# ultra-violet-tooth-sensor-mk-2_4.net
KiCad netlist of a schematic drawn in EAGLE
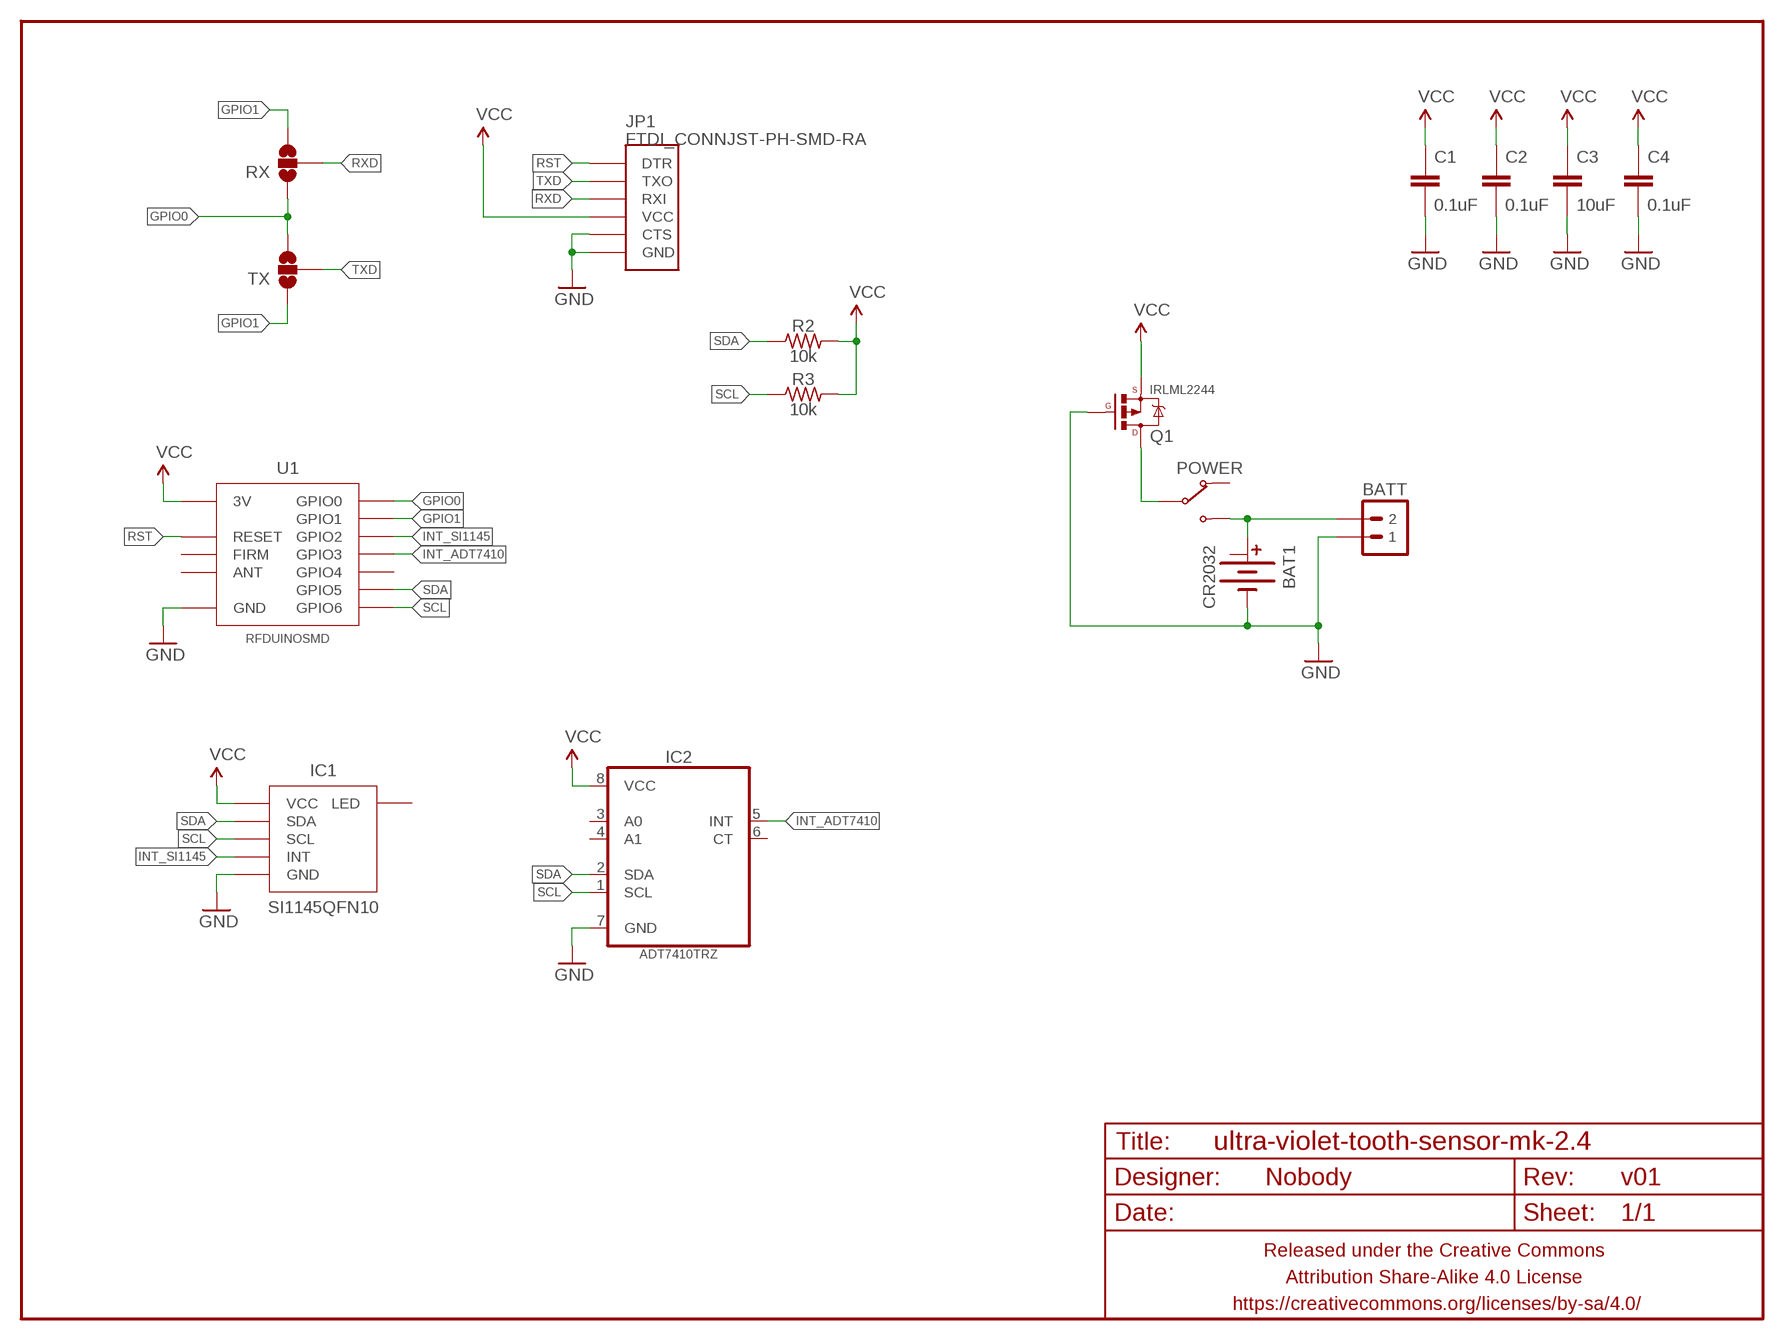
[diagram p0: schematic, sheet 1]

(export (version "E")
  (design (tool "Eeschema 10.0.6"))
  (components
    (comp (ref "BAT1")
      (value "CR2032")
      (footprint "eagle-import:BATTCON_20MM_MINE_STAHPIT")
      (libsource (lib "eagle-import") (part "BATTERY-COINCR2032_SMD_TIGHT"))
    )
    (comp (ref "BATT")
      (value "M02PTH-CENTERED-R+")
      (footprint "eagle-import:1X02-CENTER-R+")
      (libsource (lib "eagle-import") (part "M02PTH-CENTERED-R+"))
    )
    (comp (ref "C1")
      (value "0.1uF")
      (footprint "eagle-import:C0805")
      (libsource (lib "eagle-import") (part "CAPACITOR-CERAMICC0805"))
    )
    (comp (ref "C2")
      (value "0.1uF")
      (footprint "eagle-import:C0603")
      (libsource (lib "eagle-import") (part "CAPACITOR-CERAMICC0603"))
    )
    (comp (ref "C3")
      (value "10uF")
      (footprint "eagle-import:C1206")
      (libsource (lib "eagle-import") (part "CAPACITOR-CERAMICC1206"))
    )
    (comp (ref "C4")
      (value "0.1uF")
      (footprint "eagle-import:C0603")
      (libsource (lib "eagle-import") (part "CAPACITOR-CERAMICC0603"))
    )
    (comp (ref "FRAME1")
      (value "FRAME-LETTERNO_PACKAGE")
      (footprint "eagle-import:DUMMY")
      (fields (field (name "DESIGNER") "Nobody"))
      (libsource (lib "eagle-import") (part "FRAME-LETTERNO_PACKAGE"))
    )
    (comp (ref "IC1")
      (value "SI1145QFN10")
      (footprint "eagle-import:SI1145")
      (libsource (lib "eagle-import") (part "SI1145QFN10"))
    )
    (comp (ref "IC2")
      (value "ADT7410TRZ")
      (footprint "eagle-import:SOIC127P600X175-8N")
      (libsource (lib "eagle-import") (part "ADT7410TRZSOIC8N"))
    )
    (comp (ref "JP1")
      (value "FTDI_CONNJST-PH-SMD-RA")
      (footprint "eagle-import:AVRISP-JST-6-PH-RA-SMD")
      (libsource (lib "eagle-import") (part "FTDI_CONNJST-PH-SMD-RA"))
    )
    (comp (ref "POWER")
      (value "SWITCH-SPDTPTH-RA-2.54MM")
      (footprint "eagle-import:SPDT-RA-2.54MM")
      (libsource (lib "eagle-import") (part "SWITCH-SPDTPTH-RA-2.54MM"))
    )
    (comp (ref "Q1")
      (value "IRLML2244")
      (footprint "eagle-import:SOT23-3")
      (libsource (lib "eagle-import") (part "MOSFET-PCHANNELIRLML2244"))
    )
    (comp (ref "R2")
      (value "10k")
      (footprint "eagle-import:R0603")
      (libsource (lib "eagle-import") (part "RESISTORR0603"))
    )
    (comp (ref "R3")
      (value "10k")
      (footprint "eagle-import:R0603")
      (libsource (lib "eagle-import") (part "RESISTORR0603"))
    )
    (comp (ref "RX")
      (value "JUMPER-PAD-3-NOFULL_BOX_SILK")
      (footprint "eagle-import:PAD-JUMPER-3-NO_YES_SILK_FULL_BOX")
      (libsource (lib "eagle-import") (part "JUMPER-PAD-3-NOFULL_BOX_SILK"))
    )
    (comp (ref "TX")
      (value "JUMPER-PAD-3-NOFULL_BOX_SILK")
      (footprint "eagle-import:PAD-JUMPER-3-NO_YES_SILK_FULL_BOX")
      (libsource (lib "eagle-import") (part "JUMPER-PAD-3-NOFULL_BOX_SILK"))
    )
    (comp (ref "U1")
      (value "RFDUINOSMD")
      (footprint "eagle-import:RFDUINO-SMD")
      (libsource (lib "eagle-import") (part "RFDUINOSMD"))
    )
  )
  (nets
    (net (code "1") (name "GND") (class "Default")
      (node (ref "BAT1") (pin "BOTTOM") (pinfunction "-_BOTTOM") (pintype "bidirectional"))
      (node (ref "BATT") (pin "1") (pinfunction "1_1") (pintype "passive"))
      (node (ref "C1") (pin "2") (pinfunction "2_2") (pintype "passive"))
      (node (ref "C2") (pin "2") (pinfunction "2_2") (pintype "passive"))
      (node (ref "C3") (pin "2") (pinfunction "2_2") (pintype "passive"))
      (node (ref "C4") (pin "2") (pinfunction "2_2") (pintype "passive"))
      (node (ref "IC1") (pin "GND") (pinfunction "GND_GND") (pintype "bidirectional"))
      (node (ref "IC2") (pin "7") (pinfunction "GND_7") (pintype "passive"))
      (node (ref "JP1") (pin "CTS") (pinfunction "CTS_CTS") (pintype "bidirectional"))
      (node (ref "JP1") (pin "GND") (pinfunction "GND_GND") (pintype "bidirectional"))
      (node (ref "Q1") (pin "1") (pinfunction "G_1") (pintype "passive"))
      (node (ref "U1") (pin "GND@1") (pinfunction "GND_GND@1") (pintype "bidirectional"))
      (node (ref "U1") (pin "GND@2") (pinfunction "GND_GND@2") (pintype "bidirectional"))
      (node (ref "U1") (pin "GND@3") (pinfunction "GND_GND@3") (pintype "bidirectional"))
      (node (ref "U1") (pin "GND@4") (pinfunction "GND_GND@4") (pintype "bidirectional"))
      (node (ref "U1") (pin "GND@5") (pinfunction "GND_GND@5") (pintype "bidirectional"))
      (node (ref "U1") (pin "GND@6") (pinfunction "GND_GND@6") (pintype "bidirectional"))
      (node (ref "U1") (pin "GND@7") (pinfunction "GND_GND@7") (pintype "bidirectional"))
      (node (ref "U1") (pin "GND@8") (pinfunction "GND_GND@8") (pintype "bidirectional"))
    )
    (net (code "2") (name "GPIO0") (class "Default")
      (node (ref "RX") (pin "1") (pinfunction "1_1") (pintype "passive"))
      (node (ref "TX") (pin "3") (pinfunction "3_3") (pintype "passive"))
      (node (ref "U1") (pin "GPIO0") (pinfunction "GPIO0_GPIO0") (pintype "bidirectional"))
    )
    (net (code "3") (name "GPIO1") (class "Default")
      (node (ref "RX") (pin "3") (pinfunction "3_3") (pintype "passive"))
      (node (ref "TX") (pin "1") (pinfunction "1_1") (pintype "passive"))
      (node (ref "U1") (pin "GPIO1") (pinfunction "GPIO1_GPIO1") (pintype "bidirectional"))
    )
    (net (code "4") (name "INT_ADT7410") (class "Default")
      (node (ref "IC2") (pin "5") (pinfunction "INT_5") (pintype "output"))
      (node (ref "U1") (pin "GPIO3") (pinfunction "GPIO3_GPIO3") (pintype "bidirectional"))
    )
    (net (code "5") (name "INT_SI1145") (class "Default")
      (node (ref "IC1") (pin "INT") (pinfunction "INT_INT") (pintype "bidirectional"))
      (node (ref "U1") (pin "GPIO2") (pinfunction "GPIO2_GPIO2") (pintype "bidirectional"))
    )
    (net (code "6") (name "Net-(BAT1-+)") (class "Default")
      (node (ref "BAT1") (pin "TOP@1") (pinfunction "+_TOP@1") (pintype "bidirectional"))
      (node (ref "BATT") (pin "2") (pinfunction "2_2") (pintype "passive"))
      (node (ref "POWER") (pin "3") (pinfunction "NO_3") (pintype "passive"))
    )
    (net (code "7") (name "Net-(POWER-COM)") (class "Default")
      (node (ref "POWER") (pin "2") (pinfunction "COM_2") (pintype "passive"))
      (node (ref "Q1") (pin "3") (pinfunction "D_3") (pintype "passive"))
    )
    (net (code "8") (name "RST") (class "Default")
      (node (ref "JP1") (pin "DTR") (pinfunction "DTR_DTR") (pintype "bidirectional"))
      (node (ref "U1") (pin "RESET") (pinfunction "RESET_RESET") (pintype "bidirectional"))
    )
    (net (code "9") (name "RXD") (class "Default")
      (node (ref "JP1") (pin "RXI") (pinfunction "RXI_RXI") (pintype "bidirectional"))
      (node (ref "RX") (pin "2") (pinfunction "2_2") (pintype "passive"))
    )
    (net (code "10") (name "SCL") (class "Default")
      (node (ref "IC1") (pin "SCL") (pinfunction "SCL_SCL") (pintype "bidirectional"))
      (node (ref "IC2") (pin "1") (pinfunction "SCL_1") (pintype "input"))
      (node (ref "R3") (pin "1") (pinfunction "1_1") (pintype "passive"))
      (node (ref "U1") (pin "GPIO6") (pinfunction "GPIO6_GPIO6") (pintype "bidirectional"))
    )
    (net (code "11") (name "SDA") (class "Default")
      (node (ref "IC1") (pin "SDA") (pinfunction "SDA_SDA") (pintype "bidirectional"))
      (node (ref "IC2") (pin "2") (pinfunction "SDA_2") (pintype "bidirectional"))
      (node (ref "R2") (pin "1") (pinfunction "1_1") (pintype "passive"))
      (node (ref "U1") (pin "GPIO5") (pinfunction "GPIO5_GPIO5") (pintype "bidirectional"))
    )
    (net (code "12") (name "TXD") (class "Default")
      (node (ref "JP1") (pin "TXO") (pinfunction "TXO_TXO") (pintype "bidirectional"))
      (node (ref "TX") (pin "2") (pinfunction "2_2") (pintype "passive"))
    )
    (net (code "13") (name "VCC") (class "Default")
      (node (ref "C1") (pin "1") (pinfunction "1_1") (pintype "passive"))
      (node (ref "C2") (pin "1") (pinfunction "1_1") (pintype "passive"))
      (node (ref "C3") (pin "1") (pinfunction "1_1") (pintype "passive"))
      (node (ref "C4") (pin "1") (pinfunction "1_1") (pintype "passive"))
      (node (ref "IC1") (pin "VCC@1") (pinfunction "VCC_VCC@1") (pintype "bidirectional"))
      (node (ref "IC1") (pin "VCC@2") (pinfunction "VCC_VCC@2") (pintype "bidirectional"))
      (node (ref "IC1") (pin "VCC@3") (pinfunction "VCC_VCC@3") (pintype "bidirectional"))
      (node (ref "IC2") (pin "8") (pinfunction "VCC_8") (pintype "power_in"))
      (node (ref "JP1") (pin "VCC") (pinfunction "VCC_VCC") (pintype "bidirectional"))
      (node (ref "Q1") (pin "2") (pinfunction "S_2") (pintype "passive"))
      (node (ref "R2") (pin "2") (pinfunction "2_2") (pintype "passive"))
      (node (ref "R3") (pin "2") (pinfunction "2_2") (pintype "passive"))
      (node (ref "U1") (pin "3V") (pinfunction "3V_3V") (pintype "bidirectional"))
    )
    (net (code "14") (name "unconnected-(BAT1-+1-PadTOP@2)") (class "Default")
      (node (ref "BAT1") (pin "TOP@2") (pinfunction "+1_TOP@2") (pintype "bidirectional"))
    )
    (net (code "15") (name "unconnected-(IC1-PadLED)") (class "Default")
      (node (ref "IC1") (pin "LED") (pinfunction "LED_LED") (pintype "bidirectional"))
    )
    (net (code "16") (name "unconnected-(IC2-A0-Pad3)") (class "Default")
      (node (ref "IC2") (pin "3") (pinfunction "A0_3") (pintype "input"))
    )
    (net (code "17") (name "unconnected-(IC2-A1-Pad4)") (class "Default")
      (node (ref "IC2") (pin "4") (pinfunction "A1_4") (pintype "input"))
    )
    (net (code "18") (name "unconnected-(IC2-CT-Pad6)") (class "Default")
      (node (ref "IC2") (pin "6") (pinfunction "CT_6") (pintype "output"))
    )
    (net (code "19") (name "unconnected-(POWER-NC-Pad1)") (class "Default")
      (node (ref "POWER") (pin "1") (pinfunction "NC_1") (pintype "passive"))
    )
    (net (code "20") (name "unconnected-(U1-FIRM-PadFACTORY)") (class "Default")
      (node (ref "U1") (pin "FACTORY") (pinfunction "FIRM_FACTORY") (pintype "bidirectional"))
    )
    (net (code "21") (name "unconnected-(U1-PadANT)") (class "Default")
      (node (ref "U1") (pin "ANT") (pinfunction "ANT_ANT") (pintype "bidirectional"))
    )
    (net (code "22") (name "unconnected-(U1-PadGPIO4)") (class "Default")
      (node (ref "U1") (pin "GPIO4") (pinfunction "GPIO4_GPIO4") (pintype "bidirectional"))
    )
  )
)
